# HDMI_HDCP_SOCKET.net
KiCad netlist of a schematic drawn in Altium Designer
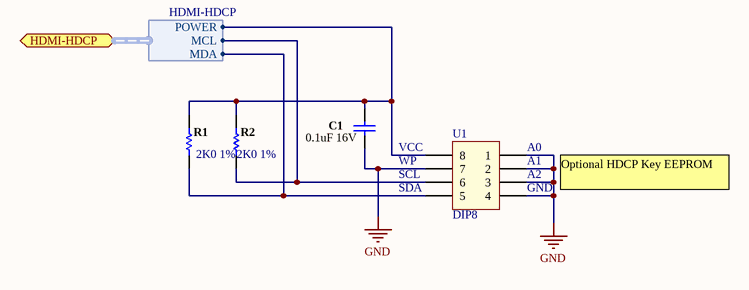
[diagram p0: HDMI_HDCP_SOCKET.SchDoc]

(export (version "E")
  (design (tool "Eeschema 10.0.6"))
  (components
    (comp (ref "C1")
      (value "0.1uF 16V")
      (footprint "CAPC1005-STAR")
      (description "Capacitor, Ceramic, 0.1uF 10% 16V 0402 (1005) X7R")
      (fields (field (name "TOLERANCE") "10 %"))
      (libsource (lib "AltiumDesignLibrary") (part "CAP-NP"))
    )
    (comp (ref "R1")
      (value "2K0 1%")
      (footprint "RESC1005-STAR")
      (description "Resistor, 2K0 1% 0402 (1005)")
      (fields (field (name "TOLERANCE") "1 %"))
      (libsource (lib "AltiumDesignLibrary") (part "RES"))
    )
    (comp (ref "R2")
      (value "2K0 1%")
      (footprint "RESC1005-STAR")
      (description "Resistor, 2K0 1% 0402 (1005)")
      (fields (field (name "TOLERANCE") "1 %"))
      (libsource (lib "AltiumDesignLibrary") (part "RES"))
    )
    (comp (ref "U1")
      (value "DIP8")
      (footprint "DIP-8-SOCKET")
      (description "Socket, DIP8, Through-hole")
      (libsource (lib "AltiumDesignLibrary") (part "DIP-8-SOCKET"))
    )
  )
  (nets
    (net (code "3") (name "GND") (class "Default")
      (node (ref "C1") (pin "2") (pinfunction "2_2") (pintype "passive"))
      (node (ref "U1") (pin "1") (pinfunction "1_1") (pintype "passive"))
      (node (ref "U1") (pin "2") (pinfunction "2_2") (pintype "passive"))
      (node (ref "U1") (pin "3") (pinfunction "3_3") (pintype "passive"))
      (node (ref "U1") (pin "4") (pinfunction "4_4") (pintype "passive"))
      (node (ref "U1") (pin "7") (pinfunction "7_7") (pintype "passive"))
    )
    (net (code "4") (name "Net-(C1-Pad1)") (class "Default")
      (node (ref "C1") (pin "1") (pinfunction "1_1") (pintype "passive"))
      (node (ref "R1") (pin "2") (pinfunction "2_2") (pintype "passive"))
      (node (ref "R2") (pin "2") (pinfunction "2_2") (pintype "passive"))
      (node (ref "U1") (pin "8") (pinfunction "8_8") (pintype "passive"))
    )
    (net (code "5") (name "Net-(R1-Pad1)") (class "Default")
      (node (ref "R1") (pin "1") (pinfunction "1_1") (pintype "passive"))
      (node (ref "U1") (pin "5") (pinfunction "5_5") (pintype "passive"))
    )
    (net (code "6") (name "Net-(R2-Pad1)") (class "Default")
      (node (ref "R2") (pin "1") (pinfunction "1_1") (pintype "passive"))
      (node (ref "U1") (pin "6") (pinfunction "6_6") (pintype "passive"))
    )
  )
)
